# Module_ReadSingleEncoderABZ.net
KiCad netlist of a schematic drawn in Altium Designer
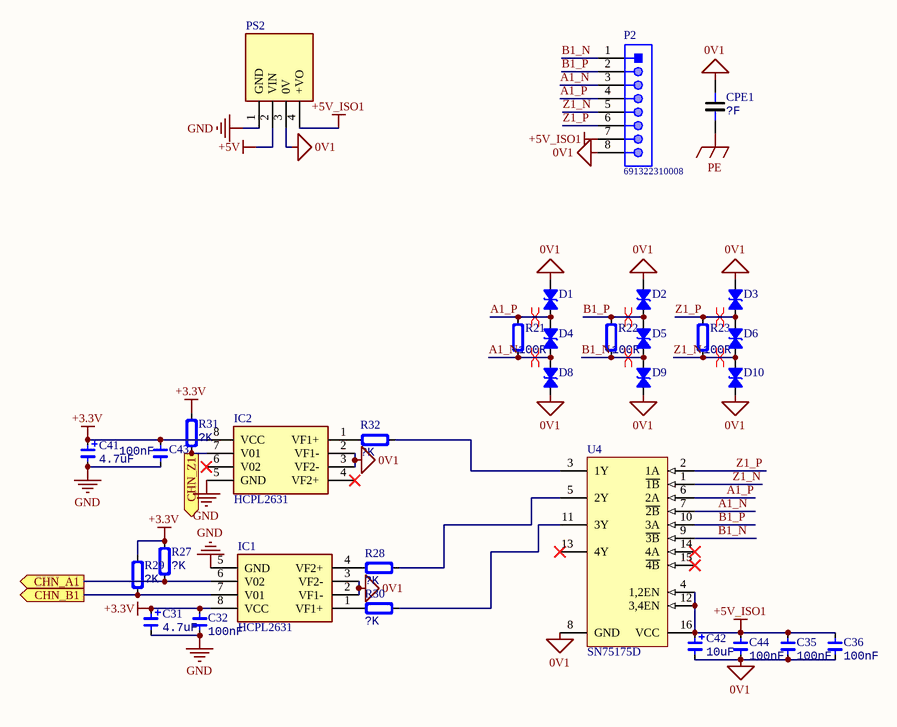
[diagram p0: [Module]ReadSingleEncoderABZ.SchDoc]

(export (version "E")
  (design (tool "Eeschema 10.0.6"))
  (components
    (comp (ref "C31")
      (value "4.7uF")
      (footprint "CAP_TAN_1206")
      (description "Capacitor Tantalum")
      (fields (field (name "Comment") "C1206"))
      (libsource (lib "Integrated_Library") (part "Cap_Tan_1206"))
    )
    (comp (ref "C32")
      (value "100nF")
      (footprint "CAP-0805")
      (description "Capacitor")
      (fields (field (name "Comment") "Cap_0805"))
      (libsource (lib "Integrated_Library") (part "Cap_0805"))
    )
    (comp (ref "C35")
      (value "100nF")
      (footprint "CAP-0603")
      (description "Capacitor")
      (fields (field (name "Comment") "Cap_0603"))
      (libsource (lib "Integrated_Library") (part "Cap_0603"))
    )
    (comp (ref "C36")
      (value "100nF")
      (footprint "CAP-0603")
      (description "Capacitor")
      (fields (field (name "Comment") "Cap_0603"))
      (libsource (lib "Integrated_Library") (part "Cap_0603"))
    )
    (comp (ref "C41")
      (value "4.7uF")
      (footprint "CAP_TAN_1206")
      (description "Capacitor Tantalum")
      (fields (field (name "Comment") "C1206"))
      (libsource (lib "Integrated_Library") (part "Cap_Tan_1206"))
    )
    (comp (ref "C42")
      (value "10uF")
      (footprint "CAP_TAN_1206")
      (description "Capacitor Tantalum")
      (fields (field (name "Comment") "C1206"))
      (libsource (lib "Integrated_Library") (part "Cap_Tan_1206"))
    )
    (comp (ref "C43")
      (value "100nF")
      (footprint "CAP-0805")
      (description "Capacitor")
      (fields (field (name "Comment") "Cap_0805"))
      (libsource (lib "Integrated_Library") (part "Cap_0805"))
    )
    (comp (ref "C44")
      (value "100nF")
      (footprint "CAP-0603")
      (description "Capacitor")
      (fields (field (name "Comment") "Cap_0603"))
      (libsource (lib "Integrated_Library") (part "Cap_0603"))
    )
    (comp (ref "CPE1")
      (value "?F")
      (footprint "CN3")
      (description "Capacitor")
      (fields (field (name "Comment") "Cap_PE"))
      (libsource (lib "Integrated_Library") (part "Cap_PE"))
    )
    (comp (ref "D1")
      (value "SOD323")
      (footprint "SOD-323")
      (description "TVS Diode")
      (libsource (lib "Integrated_Library") (part "Diode_TVS"))
    )
    (comp (ref "D2")
      (value "SOD323")
      (footprint "SOD-323")
      (description "TVS Diode")
      (libsource (lib "Integrated_Library") (part "Diode_TVS"))
    )
    (comp (ref "D3")
      (value "SOD323")
      (footprint "SOD-323")
      (description "TVS Diode")
      (libsource (lib "Integrated_Library") (part "Diode_TVS"))
    )
    (comp (ref "D4")
      (value "SOD323")
      (footprint "SOD-323")
      (description "TVS Diode")
      (libsource (lib "Integrated_Library") (part "Diode_TVS"))
    )
    (comp (ref "D5")
      (value "SOD323")
      (footprint "SOD-323")
      (description "TVS Diode")
      (libsource (lib "Integrated_Library") (part "Diode_TVS"))
    )
    (comp (ref "D6")
      (value "SOD323")
      (footprint "SOD-323")
      (description "TVS Diode")
      (libsource (lib "Integrated_Library") (part "Diode_TVS"))
    )
    (comp (ref "D8")
      (value "SOD323")
      (footprint "SOD-323")
      (description "TVS Diode")
      (libsource (lib "Integrated_Library") (part "Diode_TVS"))
    )
    (comp (ref "D9")
      (value "SOD323")
      (footprint "SOD-323")
      (description "TVS Diode")
      (libsource (lib "Integrated_Library") (part "Diode_TVS"))
    )
    (comp (ref "D10")
      (value "SOD323")
      (footprint "SOD-323")
      (description "TVS Diode")
      (libsource (lib "Integrated_Library") (part "Diode_TVS"))
    )
    (comp (ref "IC1")
      (value "HCPL2631")
      (footprint "SamacSys:DIP762W56P254L966H508Q8N")
      (description "Integrated Circuit")
      (fields (field (name "MOUSER PART NUMBER") "512-HCPL-2631"))
      (libsource (lib "*") (part "HCPL2631"))
    )
    (comp (ref "IC2")
      (value "HCPL2631")
      (footprint "SamacSys:DIP762W56P254L966H508Q8N")
      (description "Integrated Circuit")
      (fields (field (name "MOUSER PART NUMBER") "512-HCPL-2631"))
      (libsource (lib "") (part "HCPL2631_1"))
    )
    (comp (ref "P2")
      (value "691322310008")
      (footprint "691322310008")
      (description "Serie 322 - 3.81mm Horizontal PCB Header WR-TBL, 8 pin")
      (fields (field (name "MANUFACTURER") "Wurth Elektronik") (field (name "PUBLISHER") "WurthElektronik"))
      (libsource (lib "Altium Content Vault") (part "WE-CN-1P-M-R8"))
    )
    (comp (ref "PS2")
      (value "B2405S-1WR2")
      (footprint "B2405S1WR2")
      (description "Power Supply")
      (libsource (lib "Integrated_Library") (part "B2405S-1WR2"))
    )
    (comp (ref "R21")
      (value "100R")
      (footprint "RES-1206")
      (description "Resistor")
      (fields (field (name "Comment") "Res_1206"))
      (libsource (lib "Integrated_Library") (part "Res_1206"))
    )
    (comp (ref "R22")
      (value "100R")
      (footprint "RES-1206")
      (description "Resistor")
      (fields (field (name "Comment") "Res_1206"))
      (libsource (lib "Integrated_Library") (part "Res_1206"))
    )
    (comp (ref "R23")
      (value "100R")
      (footprint "RES-1206")
      (description "Resistor")
      (fields (field (name "Comment") "Res_1206"))
      (libsource (lib "Integrated_Library") (part "Res_1206"))
    )
    (comp (ref "R27")
      (value "?K")
      (footprint "RES-0805")
      (description "Resistor")
      (fields (field (name "Comment") "Res_0805"))
      (libsource (lib "Integrated_Library") (part "Res_0805"))
    )
    (comp (ref "R28")
      (value "?K")
      (footprint "RES-0805")
      (description "Resistor")
      (fields (field (name "Comment") "Res_0805"))
      (libsource (lib "Integrated_Library") (part "Res_0805"))
    )
    (comp (ref "R29")
      (value "?K")
      (footprint "RES-0805")
      (description "Resistor")
      (fields (field (name "Comment") "Res_0805"))
      (libsource (lib "Integrated_Library") (part "Res_0805"))
    )
    (comp (ref "R30")
      (value "?K")
      (footprint "RES-0805")
      (description "Resistor")
      (fields (field (name "Comment") "Res_0805"))
      (libsource (lib "Integrated_Library") (part "Res_0805"))
    )
    (comp (ref "R31")
      (value "?K")
      (footprint "RES-0805")
      (description "Resistor")
      (fields (field (name "Comment") "Res_0805"))
      (libsource (lib "Integrated_Library") (part "Res_0805"))
    )
    (comp (ref "R32")
      (value "?K")
      (footprint "RES-0805")
      (description "Resistor")
      (fields (field (name "Comment") "Res_0805"))
      (libsource (lib "Integrated_Library") (part "Res_0805"))
    )
    (comp (ref "U4")
      (value "SN75175D")
      (footprint "D0016A_M")
      (fields (field (name "MANUFACTURER") "Texas Instruments"))
      (libsource (lib "Altium Content Vault") (part "TI-SN75175-SOIC_D-16"))
    )
  )
  (nets
    (net (code "1") (name "+3.3V") (class "Default")
      (node (ref "C31") (pin "1") (pinfunction "1_1") (pintype "passive"))
      (node (ref "C32") (pin "2") (pinfunction "2_2") (pintype "passive"))
      (node (ref "C41") (pin "1") (pinfunction "1_1") (pintype "passive"))
      (node (ref "C43") (pin "2") (pinfunction "2_2") (pintype "passive"))
      (node (ref "IC1") (pin "8") (pinfunction "VCC_8") (pintype "passive"))
      (node (ref "IC2") (pin "8") (pinfunction "VCC_8") (pintype "passive"))
      (node (ref "R27") (pin "2") (pinfunction "2_2") (pintype "passive"))
      (node (ref "R29") (pin "2") (pinfunction "2_2") (pintype "passive"))
      (node (ref "R31") (pin "2") (pinfunction "2_2") (pintype "passive"))
    )
    (net (code "2") (name "+5V") (class "Default")
      (node (ref "PS2") (pin "2") (pinfunction "VIN_2") (pintype "passive"))
    )
    (net (code "3") (name "+5V_ISO1") (class "Default")
      (node (ref "C35") (pin "2") (pinfunction "2_2") (pintype "passive"))
      (node (ref "C36") (pin "2") (pinfunction "2_2") (pintype "passive"))
      (node (ref "C42") (pin "1") (pinfunction "1_1") (pintype "passive"))
      (node (ref "C44") (pin "2") (pinfunction "2_2") (pintype "passive"))
      (node (ref "P2") (pin "7") (pinfunction "7_7") (pintype "passive"))
      (node (ref "PS2") (pin "4") (pinfunction "+VO_4") (pintype "passive"))
      (node (ref "U4") (pin "12") (pinfunction "3,4EN_12") (pintype "input"))
      (node (ref "U4") (pin "16") (pinfunction "VCC_16") (pintype "power_in"))
      (node (ref "U4") (pin "4") (pinfunction "1,2EN_4") (pintype "input"))
    )
    (net (code "4") (name "/A1_N") (class "Default")
      (node (ref "D4") (pin "1") (pinfunction "A_1") (pintype "passive"))
      (node (ref "D8") (pin "2") (pinfunction "K_2") (pintype "passive"))
      (node (ref "P2") (pin "3") (pinfunction "3_3") (pintype "passive"))
      (node (ref "R21") (pin "1") (pinfunction "1_1") (pintype "passive"))
      (node (ref "U4") (pin "7") (pinfunction "~{2B}_7") (pintype "input"))
    )
    (net (code "5") (name "/A1_P") (class "Default")
      (node (ref "D1") (pin "1") (pinfunction "A_1") (pintype "passive"))
      (node (ref "D4") (pin "2") (pinfunction "K_2") (pintype "passive"))
      (node (ref "P2") (pin "4") (pinfunction "4_4") (pintype "passive"))
      (node (ref "R21") (pin "2") (pinfunction "2_2") (pintype "passive"))
      (node (ref "U4") (pin "6") (pinfunction "2A_6") (pintype "input"))
    )
    (net (code "6") (name "/B1_N") (class "Default")
      (node (ref "D5") (pin "1") (pinfunction "A_1") (pintype "passive"))
      (node (ref "D9") (pin "2") (pinfunction "K_2") (pintype "passive"))
      (node (ref "P2") (pin "1") (pinfunction "1_1") (pintype "passive"))
      (node (ref "R22") (pin "1") (pinfunction "1_1") (pintype "passive"))
      (node (ref "U4") (pin "9") (pinfunction "~{3B}_9") (pintype "input"))
    )
    (net (code "7") (name "/B1_P") (class "Default")
      (node (ref "D2") (pin "1") (pinfunction "A_1") (pintype "passive"))
      (node (ref "D5") (pin "2") (pinfunction "K_2") (pintype "passive"))
      (node (ref "P2") (pin "2") (pinfunction "2_2") (pintype "passive"))
      (node (ref "R22") (pin "2") (pinfunction "2_2") (pintype "passive"))
      (node (ref "U4") (pin "10") (pinfunction "3A_10") (pintype "input"))
    )
    (net (code "8") (name "/CHN_A1") (class "Default")
      (node (ref "IC1") (pin "6") (pinfunction "V02_6") (pintype "passive"))
      (node (ref "R27") (pin "1") (pinfunction "1_1") (pintype "passive"))
    )
    (net (code "9") (name "/CHN_B1") (class "Default")
      (node (ref "IC1") (pin "7") (pinfunction "V01_7") (pintype "passive"))
      (node (ref "R29") (pin "1") (pinfunction "1_1") (pintype "passive"))
    )
    (net (code "10") (name "/CHN_Z1") (class "Default")
      (node (ref "IC2") (pin "7") (pinfunction "V01_7") (pintype "passive"))
      (node (ref "R31") (pin "1") (pinfunction "1_1") (pintype "passive"))
    )
    (net (code "11") (name "/Z1_N") (class "Default")
      (node (ref "D10") (pin "2") (pinfunction "K_2") (pintype "passive"))
      (node (ref "D6") (pin "1") (pinfunction "A_1") (pintype "passive"))
      (node (ref "P2") (pin "5") (pinfunction "5_5") (pintype "passive"))
      (node (ref "R23") (pin "1") (pinfunction "1_1") (pintype "passive"))
      (node (ref "U4") (pin "1") (pinfunction "~{1B}_1") (pintype "input"))
    )
    (net (code "12") (name "/Z1_P") (class "Default")
      (node (ref "D3") (pin "1") (pinfunction "A_1") (pintype "passive"))
      (node (ref "D6") (pin "2") (pinfunction "K_2") (pintype "passive"))
      (node (ref "P2") (pin "6") (pinfunction "6_6") (pintype "passive"))
      (node (ref "R23") (pin "2") (pinfunction "2_2") (pintype "passive"))
      (node (ref "U4") (pin "2") (pinfunction "1A_2") (pintype "input"))
    )
    (net (code "13") (name "0V1") (class "Default")
      (node (ref "C35") (pin "1") (pinfunction "1_1") (pintype "passive"))
      (node (ref "C36") (pin "1") (pinfunction "1_1") (pintype "passive"))
      (node (ref "C42") (pin "2") (pinfunction "2_2") (pintype "passive"))
      (node (ref "C44") (pin "1") (pinfunction "1_1") (pintype "passive"))
      (node (ref "CPE1") (pin "2") (pinfunction "2_2") (pintype "passive"))
      (node (ref "D1") (pin "2") (pinfunction "K_2") (pintype "passive"))
      (node (ref "D10") (pin "1") (pinfunction "A_1") (pintype "passive"))
      (node (ref "D2") (pin "2") (pinfunction "K_2") (pintype "passive"))
      (node (ref "D3") (pin "2") (pinfunction "K_2") (pintype "passive"))
      (node (ref "D8") (pin "1") (pinfunction "A_1") (pintype "passive"))
      (node (ref "D9") (pin "1") (pinfunction "A_1") (pintype "passive"))
      (node (ref "IC1") (pin "2") (pinfunction "VF1-_2") (pintype "passive"))
      (node (ref "IC1") (pin "3") (pinfunction "VF2-_3") (pintype "passive"))
      (node (ref "IC2") (pin "2") (pinfunction "VF1-_2") (pintype "passive"))
      (node (ref "IC2") (pin "3") (pinfunction "VF2-_3") (pintype "passive"))
      (node (ref "P2") (pin "8") (pinfunction "8_8") (pintype "passive"))
      (node (ref "PS2") (pin "3") (pinfunction "0V_3") (pintype "passive"))
      (node (ref "U4") (pin "8") (pinfunction "GND_8") (pintype "power_in"))
    )
    (net (code "14") (name "GND") (class "Default")
      (node (ref "C31") (pin "2") (pinfunction "2_2") (pintype "passive"))
      (node (ref "C32") (pin "1") (pinfunction "1_1") (pintype "passive"))
      (node (ref "C41") (pin "2") (pinfunction "2_2") (pintype "passive"))
      (node (ref "C43") (pin "1") (pinfunction "1_1") (pintype "passive"))
      (node (ref "IC1") (pin "5") (pinfunction "GND_5") (pintype "passive"))
      (node (ref "IC2") (pin "5") (pinfunction "GND_5") (pintype "passive"))
      (node (ref "PS2") (pin "1") (pinfunction "GND_1") (pintype "passive"))
    )
    (net (code "15") (name "Net-(IC1-VF1+)") (class "Default")
      (node (ref "IC1") (pin "1") (pinfunction "VF1+_1") (pintype "passive"))
      (node (ref "R30") (pin "2") (pinfunction "2_2") (pintype "passive"))
    )
    (net (code "16") (name "Net-(IC1-VF2+)") (class "Default")
      (node (ref "IC1") (pin "4") (pinfunction "VF2+_4") (pintype "passive"))
      (node (ref "R28") (pin "2") (pinfunction "2_2") (pintype "passive"))
    )
    (net (code "17") (name "Net-(IC2-VF1+)") (class "Default")
      (node (ref "IC2") (pin "1") (pinfunction "VF1+_1") (pintype "passive"))
      (node (ref "R32") (pin "2") (pinfunction "2_2") (pintype "passive"))
    )
    (net (code "18") (name "Net-(U4-1Y)") (class "Default")
      (node (ref "R32") (pin "1") (pinfunction "1_1") (pintype "passive"))
      (node (ref "U4") (pin "3") (pinfunction "1Y_3") (pintype "tri_state"))
    )
    (net (code "19") (name "Net-(U4-2Y)") (class "Default")
      (node (ref "R28") (pin "1") (pinfunction "1_1") (pintype "passive"))
      (node (ref "U4") (pin "5") (pinfunction "2Y_5") (pintype "tri_state"))
    )
    (net (code "20") (name "Net-(U4-3Y)") (class "Default")
      (node (ref "R30") (pin "1") (pinfunction "1_1") (pintype "passive"))
      (node (ref "U4") (pin "11") (pinfunction "3Y_11") (pintype "tri_state"))
    )
    (net (code "21") (name "PE") (class "Default")
      (node (ref "CPE1") (pin "1") (pinfunction "1_1") (pintype "passive"))
    )
    (net (code "22") (name "unconnected-(IC2-V02-Pad6)") (class "Default")
      (node (ref "IC2") (pin "6") (pinfunction "V02_6") (pintype "passive+no_connect"))
    )
    (net (code "23") (name "unconnected-(IC2-VF2+-Pad4)") (class "Default")
      (node (ref "IC2") (pin "4") (pinfunction "VF2+_4") (pintype "passive+no_connect"))
    )
    (net (code "24") (name "unconnected-(U4-4A-Pad14)") (class "Default")
      (node (ref "U4") (pin "14") (pinfunction "4A_14") (pintype "input+no_connect"))
    )
    (net (code "25") (name "unconnected-(U4-4Y-Pad13)") (class "Default")
      (node (ref "U4") (pin "13") (pinfunction "4Y_13") (pintype "tri_state+no_connect"))
    )
    (net (code "26") (name "unconnected-(U4-~{4B}-Pad15)") (class "Default")
      (node (ref "U4") (pin "15") (pinfunction "~{4B}_15") (pintype "input+no_connect"))
    )
  )
)
